# ETHERNET.net
KiCad netlist of a schematic drawn in Altium Designer
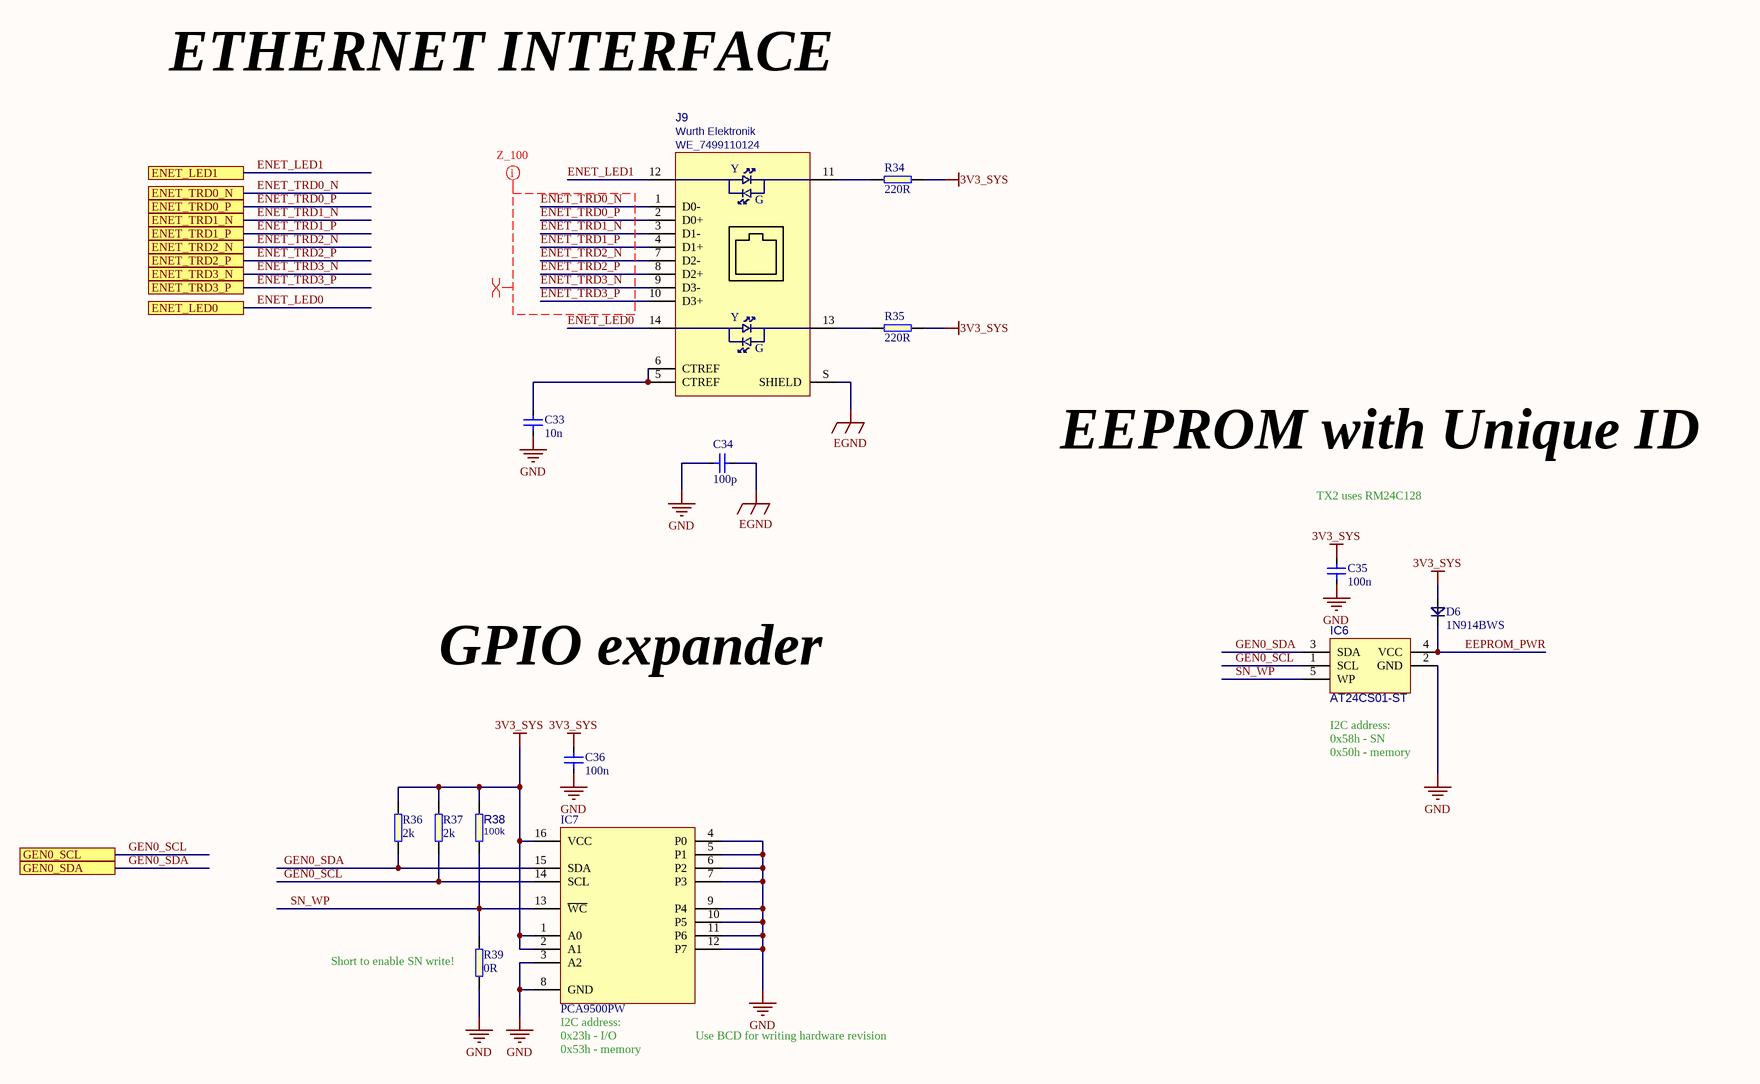
[diagram p0: ETHERNET.SchDoc]

(export (version "E")
  (design (tool "Eeschema 10.0.6"))
  (components
    (comp (ref "C33")
      (value "10n")
      (footprint "C0402")
      (description "MLCC SMT Capacitor 10 nF 0402")
      (fields (field (name "PARTNUMBER") "C_10n_0402") (field (name "MANUFACTURER") "AVX"))
      (libsource (lib "jetson-nano-baseboard") (part "C_10n_0402"))
    )
    (comp (ref "C34")
      (value "100p")
      (footprint "0805")
      (description "MLCC SMT Capacitor 100pF 0805")
      (fields (field (name "PARTNUMBER") "C_100p_0805"))
      (libsource (lib "jetson-nano-baseboard") (part "C_47u_0805"))
    )
    (comp (ref "C35")
      (value "100n")
      (footprint "C0402")
      (description "MLCC SMT Capacitor 100n 0402")
      (fields (field (name "PARTNUMBER") "C_100n_0402") (field (name "MANUFACTURER") "TDK"))
      (libsource (lib "jetson-nano-baseboard") (part "C_100n_0402"))
    )
    (comp (ref "C36")
      (value "100n")
      (footprint "C0402")
      (description "MLCC SMT Capacitor 100n 0402")
      (fields (field (name "PARTNUMBER") "C_100n_0402") (field (name "MANUFACTURER") "TDK"))
      (libsource (lib "jetson-nano-baseboard") (part "C_100n_0402"))
    )
    (comp (ref "D6")
      (value "1N914BWS")
      (footprint "SOD-323")
      (description "Diode small signal")
      (fields (field (name "MANUFACTURER") "ON SEMICONDUCTOR"))
      (libsource (lib "jetson-nano-baseboard") (part "diode"))
    )
    (comp (ref "IC6")
      (value "AT24CS01-ST")
      (footprint "SOT23-5")
      (fields (field (name "MANUFACTURER") "Atmel"))
      (libsource (lib "jetson-nano-baseboard") (part "AT24CS01"))
    )
    (comp (ref "IC7")
      (value "PCA9500PW")
      (footprint "TSSOP-16")
      (description "Remote 8bit I2C SMBus I/O expander w/ 2kbit EEPROM memory")
      (fields (field (name "MANUFACTURER") "NXP Semicondutors"))
      (libsource (lib "jetson-nano-baseboard") (part "PCA9500PW"))
    )
    (comp (ref "J9")
      (value "WE_7499110124")
      (footprint "WE_7499110124")
      (description "LAN-Transformer WE-RJ45LAN 10/100/1000 BaseT")
      (fields (field (name "MANUFACTURER") "Wurth Elektronik") (field (name "PARTSYMBOL") "WE_7499110124"))
      (libsource (lib "jetson-nano-baseboard") (part "WE_7499111447"))
    )
    (comp (ref "R34")
      (value "220R")
      (footprint "R0402")
      (description "RES, 220R, 0402")
      (fields (field (name "PARTNUMBER") "R_220R_0402") (field (name "MANUFACTURER") "TE CONECTIVITY"))
      (libsource (lib "jetson-nano-baseboard") (part "R_220R_0402"))
    )
    (comp (ref "R35")
      (value "220R")
      (footprint "R0402")
      (description "RES, 220R, 0402")
      (fields (field (name "PARTNUMBER") "R_220R_0402") (field (name "MANUFACTURER") "TE CONECTIVITY"))
      (libsource (lib "jetson-nano-baseboard") (part "R_220R_0402"))
    )
    (comp (ref "R36")
      (value "2k")
      (footprint "R0402")
      (description "RES, 2k, 0402")
      (fields (field (name "PARTNUMBER") "R_2k_0402") (field (name "MANUFACTURER") "VISHAY"))
      (libsource (lib "jetson-nano-baseboard") (part "R_2k_0402"))
    )
    (comp (ref "R37")
      (value "2k")
      (footprint "R0402")
      (description "RES, 2k, 0402")
      (fields (field (name "PARTNUMBER") "R_2k_0402") (field (name "MANUFACTURER") "VISHAY"))
      (libsource (lib "jetson-nano-baseboard") (part "R_2k_0402"))
    )
    (comp (ref "R38")
      (value "100k")
      (footprint "R0402")
      (description "SMT Resistor 100k 0402")
      (fields (field (name "PARTNUMBER") "R_100k_0402") (field (name "TOLERANCE") "1%"))
      (libsource (lib "jetson-nano-baseboard") (part "R_100k_0402"))
    )
    (comp (ref "R39")
      (value "0R")
      (footprint "R0402")
      (description "RES, 0R, 0402")
      (fields (field (name "PARTNUMBER") "R_0R_0402") (field (name "MANUFACTURER") "Panasonic"))
      (libsource (lib "jetson-nano-baseboard") (part "R_0R_0402"))
    )
  )
  (nets
    (net (code "1") (name "/EEPROM_PWR") (class "Default")
      (node (ref "D6") (pin "C") (pinfunction "C_C") (pintype "passive"))
      (node (ref "IC6") (pin "4") (pinfunction "VCC_4") (pintype "passive"))
    )
    (net (code "2") (name "/ENET_LED0") (class "Default")
      (node (ref "J9") (pin "14") (pinfunction "14_14") (pintype "passive"))
    )
    (net (code "3") (name "/ENET_LED1") (class "Default")
      (node (ref "J9") (pin "12") (pinfunction "12_12") (pintype "passive"))
    )
    (net (code "4") (name "/ENET_TRD0_N") (class "Default")
      (node (ref "J9") (pin "1") (pinfunction "D0-_1") (pintype "passive"))
    )
    (net (code "5") (name "/ENET_TRD0_P") (class "Default")
      (node (ref "J9") (pin "2") (pinfunction "D0+_2") (pintype "passive"))
    )
    (net (code "6") (name "/ENET_TRD1_N") (class "Default")
      (node (ref "J9") (pin "3") (pinfunction "D1-_3") (pintype "passive"))
    )
    (net (code "7") (name "/ENET_TRD1_P") (class "Default")
      (node (ref "J9") (pin "4") (pinfunction "D1+_4") (pintype "passive"))
    )
    (net (code "8") (name "/ENET_TRD2_N") (class "Default")
      (node (ref "J9") (pin "7") (pinfunction "D2-_7") (pintype "passive"))
    )
    (net (code "9") (name "/ENET_TRD2_P") (class "Default")
      (node (ref "J9") (pin "8") (pinfunction "D2+_8") (pintype "passive"))
    )
    (net (code "10") (name "/ENET_TRD3_N") (class "Default")
      (node (ref "J9") (pin "9") (pinfunction "D3-_9") (pintype "passive"))
    )
    (net (code "11") (name "/ENET_TRD3_P") (class "Default")
      (node (ref "J9") (pin "10") (pinfunction "D3+_10") (pintype "passive"))
    )
    (net (code "12") (name "/GEN0_SCL") (class "Default")
      (node (ref "IC6") (pin "1") (pinfunction "SCL_1") (pintype "passive"))
      (node (ref "IC7") (pin "14") (pinfunction "SCL_14") (pintype "passive"))
      (node (ref "R37") (pin "1") (pintype "passive"))
    )
    (net (code "13") (name "/GEN0_SDA") (class "Default")
      (node (ref "IC6") (pin "3") (pinfunction "SDA_3") (pintype "passive"))
      (node (ref "IC7") (pin "15") (pinfunction "SDA_15") (pintype "passive"))
      (node (ref "R36") (pin "1") (pintype "passive"))
    )
    (net (code "14") (name "/SN_WP") (class "Default")
      (node (ref "IC6") (pin "5") (pinfunction "WP_5") (pintype "passive"))
      (node (ref "IC7") (pin "13") (pinfunction "~{WC}_13") (pintype "passive"))
      (node (ref "R38") (pin "2") (pintype "passive"))
      (node (ref "R39") (pin "2") (pintype "passive"))
    )
    (net (code "15") (name "3V3_SYS") (class "Default")
      (node (ref "C35") (pin "2") (pinfunction "2_2") (pintype "passive"))
      (node (ref "C36") (pin "2") (pinfunction "2_2") (pintype "passive"))
      (node (ref "D6") (pin "A") (pinfunction "A_A") (pintype "passive"))
      (node (ref "IC7") (pin "1") (pinfunction "A0_1") (pintype "passive"))
      (node (ref "IC7") (pin "16") (pinfunction "VCC_16") (pintype "passive"))
      (node (ref "IC7") (pin "2") (pinfunction "A1_2") (pintype "passive"))
      (node (ref "R34") (pin "2") (pintype "passive"))
      (node (ref "R35") (pin "2") (pintype "passive"))
      (node (ref "R36") (pin "2") (pintype "passive"))
      (node (ref "R37") (pin "2") (pintype "passive"))
      (node (ref "R38") (pin "1") (pintype "passive"))
    )
    (net (code "16") (name "EGND") (class "Default")
      (node (ref "C34") (pin "2") (pinfunction "2_2") (pintype "passive"))
      (node (ref "J9") (pin "S") (pinfunction "SHIELD_S") (pintype "passive"))
    )
    (net (code "17") (name "GND") (class "Default")
      (node (ref "C33") (pin "1") (pinfunction "1_1") (pintype "passive"))
      (node (ref "C34") (pin "1") (pinfunction "1_1") (pintype "passive"))
      (node (ref "C35") (pin "1") (pinfunction "1_1") (pintype "passive"))
      (node (ref "C36") (pin "1") (pinfunction "1_1") (pintype "passive"))
      (node (ref "IC6") (pin "2") (pinfunction "GND_2") (pintype "passive"))
      (node (ref "IC7") (pin "10") (pinfunction "P5_10") (pintype "passive"))
      (node (ref "IC7") (pin "11") (pinfunction "P6_11") (pintype "passive"))
      (node (ref "IC7") (pin "12") (pinfunction "P7_12") (pintype "passive"))
      (node (ref "IC7") (pin "3") (pinfunction "A2_3") (pintype "passive"))
      (node (ref "IC7") (pin "4") (pinfunction "P0_4") (pintype "passive"))
      (node (ref "IC7") (pin "5") (pinfunction "P1_5") (pintype "passive"))
      (node (ref "IC7") (pin "6") (pinfunction "P2_6") (pintype "passive"))
      (node (ref "IC7") (pin "7") (pinfunction "P3_7") (pintype "passive"))
      (node (ref "IC7") (pin "8") (pinfunction "GND_8") (pintype "passive"))
      (node (ref "IC7") (pin "9") (pinfunction "P4_9") (pintype "passive"))
      (node (ref "R39") (pin "1") (pintype "passive"))
    )
    (net (code "18") (name "Net-(C33-Pad2)") (class "Default")
      (node (ref "C33") (pin "2") (pinfunction "2_2") (pintype "passive"))
      (node (ref "J9") (pin "5") (pinfunction "CTREF_5") (pintype "passive"))
      (node (ref "J9") (pin "6") (pinfunction "CTREF_6") (pintype "passive"))
    )
    (net (code "19") (name "Net-(J9-Pad11)") (class "Default")
      (node (ref "J9") (pin "11") (pinfunction "11_11") (pintype "passive"))
      (node (ref "R34") (pin "1") (pintype "passive"))
    )
    (net (code "20") (name "Net-(J9-Pad13)") (class "Default")
      (node (ref "J9") (pin "13") (pinfunction "13_13") (pintype "passive"))
      (node (ref "R35") (pin "1") (pintype "passive"))
    )
  )
)
